# CAN.net
KiCad netlist of a schematic drawn in Altium Designer
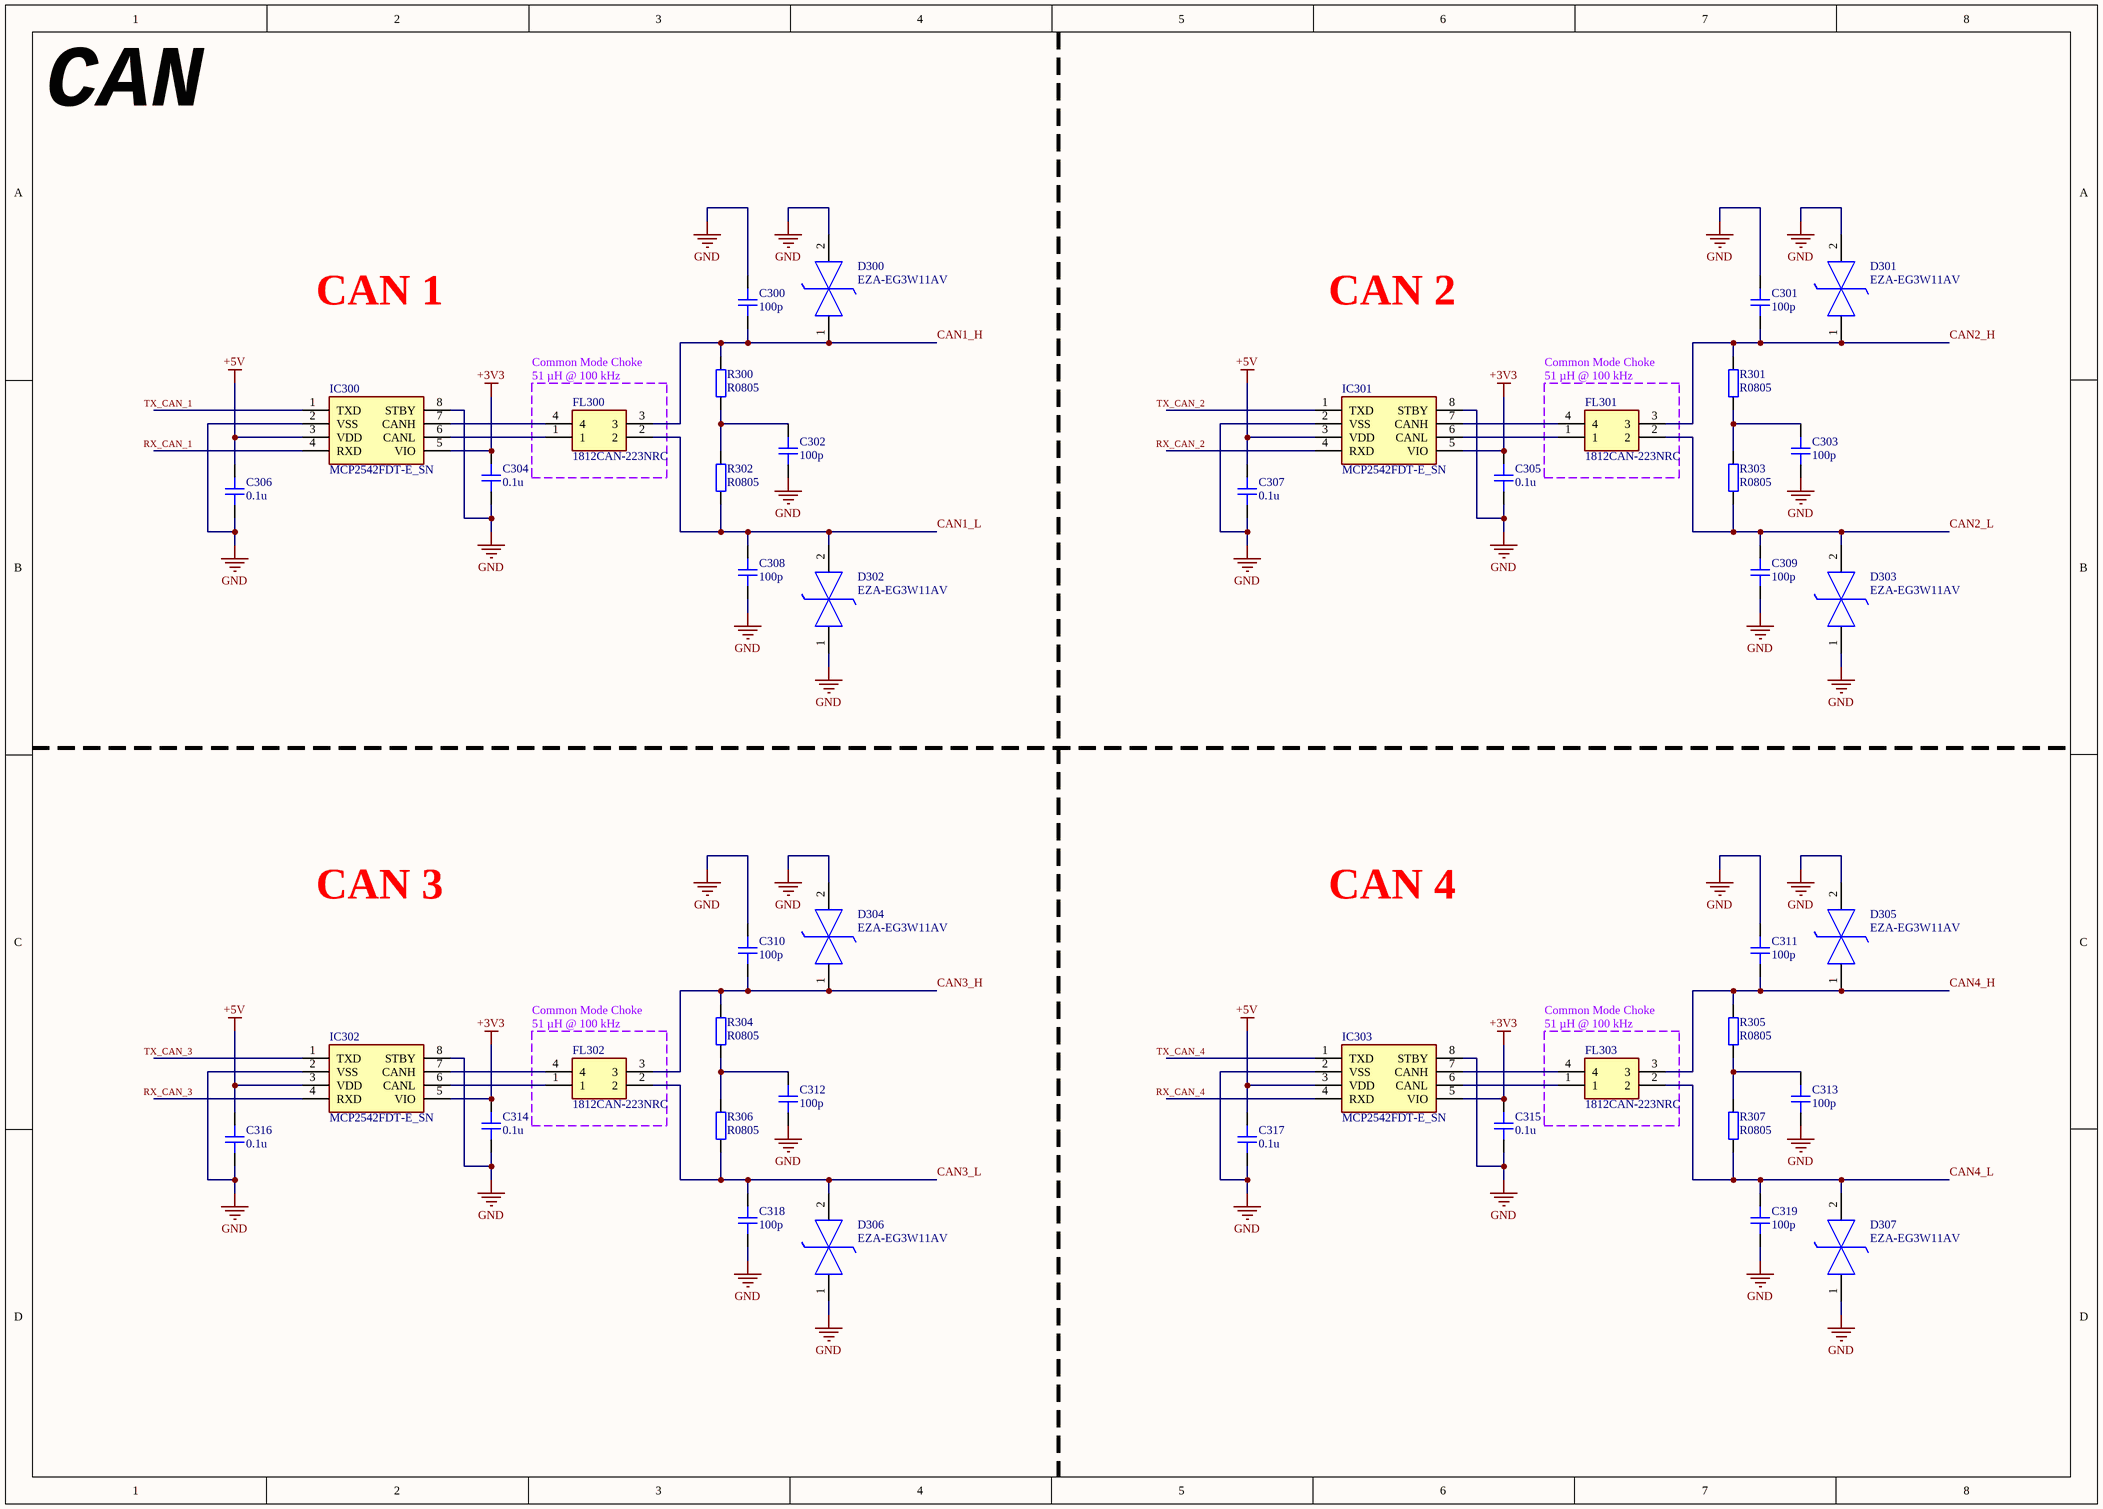
[diagram p0: CAN.SchDoc]

(export (version "E")
  (design (tool "Eeschema 10.0.6"))
  (components
    (comp (ref "C300")
      (value "100p")
      (footprint "CAP_0805")
      (description "Capacitor SMD 0805 10V")
      (libsource (lib "Schematic-Lib-PhilsLab") (part "CAP_0805_10V"))
    )
    (comp (ref "C301")
      (value "100p")
      (footprint "CAP_0805")
      (description "Capacitor SMD 0805 10V")
      (libsource (lib "Schematic-Lib-PhilsLab") (part "CAP_0805_10V"))
    )
    (comp (ref "C302")
      (value "100p")
      (footprint "CAP_0805")
      (description "Capacitor SMD 0805 10V")
      (libsource (lib "Schematic-Lib-PhilsLab") (part "CAP_0805_10V"))
    )
    (comp (ref "C303")
      (value "100p")
      (footprint "CAP_0805")
      (description "Capacitor SMD 0805 10V")
      (libsource (lib "Schematic-Lib-PhilsLab") (part "CAP_0805_10V"))
    )
    (comp (ref "C304")
      (value "0.1u")
      (footprint "CAP_0805")
      (description "Capacitor SMD 0805 10V")
      (libsource (lib "Schematic-Lib-PhilsLab") (part "CAP_0805_10V"))
    )
    (comp (ref "C305")
      (value "0.1u")
      (footprint "CAP_0805")
      (description "Capacitor SMD 0805 10V")
      (libsource (lib "Schematic-Lib-PhilsLab") (part "CAP_0805_10V"))
    )
    (comp (ref "C306")
      (value "0.1u")
      (footprint "CAP_0805")
      (description "Capacitor SMD 0805 10V")
      (libsource (lib "Schematic-Lib-PhilsLab") (part "CAP_0805_10V"))
    )
    (comp (ref "C307")
      (value "0.1u")
      (footprint "CAP_0805")
      (description "Capacitor SMD 0805 10V")
      (libsource (lib "Schematic-Lib-PhilsLab") (part "CAP_0805_10V"))
    )
    (comp (ref "C308")
      (value "100p")
      (footprint "CAP_0805")
      (description "Capacitor SMD 0805 10V")
      (libsource (lib "Schematic-Lib-PhilsLab") (part "CAP_0805_10V"))
    )
    (comp (ref "C309")
      (value "100p")
      (footprint "CAP_0805")
      (description "Capacitor SMD 0805 10V")
      (libsource (lib "Schematic-Lib-PhilsLab") (part "CAP_0805_10V"))
    )
    (comp (ref "C310")
      (value "100p")
      (footprint "CAP_0805")
      (description "Capacitor SMD 0805 10V")
      (libsource (lib "Schematic-Lib-PhilsLab") (part "CAP_0805_10V"))
    )
    (comp (ref "C311")
      (value "100p")
      (footprint "CAP_0805")
      (description "Capacitor SMD 0805 10V")
      (libsource (lib "Schematic-Lib-PhilsLab") (part "CAP_0805_10V"))
    )
    (comp (ref "C312")
      (value "100p")
      (footprint "CAP_0805")
      (description "Capacitor SMD 0805 10V")
      (libsource (lib "Schematic-Lib-PhilsLab") (part "CAP_0805_10V"))
    )
    (comp (ref "C313")
      (value "100p")
      (footprint "CAP_0805")
      (description "Capacitor SMD 0805 10V")
      (libsource (lib "Schematic-Lib-PhilsLab") (part "CAP_0805_10V"))
    )
    (comp (ref "C314")
      (value "0.1u")
      (footprint "CAP_0805")
      (description "Capacitor SMD 0805 10V")
      (libsource (lib "Schematic-Lib-PhilsLab") (part "CAP_0805_10V"))
    )
    (comp (ref "C315")
      (value "0.1u")
      (footprint "CAP_0805")
      (description "Capacitor SMD 0805 10V")
      (libsource (lib "Schematic-Lib-PhilsLab") (part "CAP_0805_10V"))
    )
    (comp (ref "C316")
      (value "0.1u")
      (footprint "CAP_0805")
      (description "Capacitor SMD 0805 10V")
      (libsource (lib "Schematic-Lib-PhilsLab") (part "CAP_0805_10V"))
    )
    (comp (ref "C317")
      (value "0.1u")
      (footprint "CAP_0805")
      (description "Capacitor SMD 0805 10V")
      (libsource (lib "Schematic-Lib-PhilsLab") (part "CAP_0805_10V"))
    )
    (comp (ref "C318")
      (value "100p")
      (footprint "CAP_0805")
      (description "Capacitor SMD 0805 10V")
      (libsource (lib "Schematic-Lib-PhilsLab") (part "CAP_0805_10V"))
    )
    (comp (ref "C319")
      (value "100p")
      (footprint "CAP_0805")
      (description "Capacitor SMD 0805 10V")
      (libsource (lib "Schematic-Lib-PhilsLab") (part "CAP_0805_10V"))
    )
    (comp (ref "D300")
      (value "EZA-EG3W11AV")
      (footprint "EZAEG3W11AV")
      (description "Diode ESD (Bi-directional)")
      (fields (field (name "MOUSER PART NUMBER") "667-EZA-EG3W11AV"))
      (libsource (lib "Pedro_Integrated_Library") (part "EZA-EG3W11AV"))
    )
    (comp (ref "D301")
      (value "EZA-EG3W11AV")
      (footprint "EZAEG3W11AV")
      (description "Diode ESD (Bi-directional)")
      (fields (field (name "MOUSER PART NUMBER") "667-EZA-EG3W11AV"))
      (libsource (lib "Pedro_Integrated_Library") (part "EZA-EG3W11AV"))
    )
    (comp (ref "D302")
      (value "EZA-EG3W11AV")
      (footprint "EZAEG3W11AV")
      (description "Diode ESD (Bi-directional)")
      (fields (field (name "MOUSER PART NUMBER") "667-EZA-EG3W11AV"))
      (libsource (lib "Pedro_Integrated_Library") (part "EZA-EG3W11AV"))
    )
    (comp (ref "D303")
      (value "EZA-EG3W11AV")
      (footprint "EZAEG3W11AV")
      (description "Diode ESD (Bi-directional)")
      (fields (field (name "MOUSER PART NUMBER") "667-EZA-EG3W11AV"))
      (libsource (lib "Pedro_Integrated_Library") (part "EZA-EG3W11AV"))
    )
    (comp (ref "D304")
      (value "EZA-EG3W11AV")
      (footprint "EZAEG3W11AV")
      (description "Diode ESD (Bi-directional)")
      (fields (field (name "MOUSER PART NUMBER") "667-EZA-EG3W11AV"))
      (libsource (lib "Pedro_Integrated_Library") (part "EZA-EG3W11AV"))
    )
    (comp (ref "D305")
      (value "EZA-EG3W11AV")
      (footprint "EZAEG3W11AV")
      (description "Diode ESD (Bi-directional)")
      (fields (field (name "MOUSER PART NUMBER") "667-EZA-EG3W11AV"))
      (libsource (lib "Pedro_Integrated_Library") (part "EZA-EG3W11AV"))
    )
    (comp (ref "D306")
      (value "EZA-EG3W11AV")
      (footprint "EZAEG3W11AV")
      (description "Diode ESD (Bi-directional)")
      (fields (field (name "MOUSER PART NUMBER") "667-EZA-EG3W11AV"))
      (libsource (lib "Pedro_Integrated_Library") (part "EZA-EG3W11AV"))
    )
    (comp (ref "D307")
      (value "EZA-EG3W11AV")
      (footprint "EZAEG3W11AV")
      (description "Diode ESD (Bi-directional)")
      (fields (field (name "MOUSER PART NUMBER") "667-EZA-EG3W11AV"))
      (libsource (lib "Pedro_Integrated_Library") (part "EZA-EG3W11AV"))
    )
    (comp (ref "FL300")
      (value "1812CAN-223NRC")
      (footprint "1812CAN223NRC")
      (description "Filter")
      (fields (field (name "MOUSER PART NUMBER") "994-1812CAN-223NRC"))
      (libsource (lib "Pedro_Integrated_Library") (part "1812CAN-223NRC"))
    )
    (comp (ref "FL301")
      (value "1812CAN-223NRC")
      (footprint "1812CAN223NRC")
      (description "Filter")
      (fields (field (name "MOUSER PART NUMBER") "994-1812CAN-223NRC"))
      (libsource (lib "Pedro_Integrated_Library") (part "1812CAN-223NRC"))
    )
    (comp (ref "FL302")
      (value "1812CAN-223NRC")
      (footprint "1812CAN223NRC")
      (description "Filter")
      (fields (field (name "MOUSER PART NUMBER") "994-1812CAN-223NRC"))
      (libsource (lib "Pedro_Integrated_Library") (part "1812CAN-223NRC"))
    )
    (comp (ref "FL303")
      (value "1812CAN-223NRC")
      (footprint "1812CAN223NRC")
      (description "Filter")
      (fields (field (name "MOUSER PART NUMBER") "994-1812CAN-223NRC"))
      (libsource (lib "Pedro_Integrated_Library") (part "1812CAN-223NRC"))
    )
    (comp (ref "IC300")
      (value "MCP2542FDT-E_SN")
      (footprint "SOIC127P600X175-8N")
      (description "Integrated Circuit")
      (fields
        (field (name "MANUFACTURER_PART_NUMBER") "MCP2542FDT-E/SN")
        (field (name "MOUSER PART NUMBER") "579-MCP2542FDT-E/SN")
      )
      (libsource (lib "*") (part "MCP2542FDT-E_SN"))
    )
    (comp (ref "IC301")
      (value "MCP2542FDT-E_SN")
      (footprint "SOIC127P600X175-8N")
      (description "Integrated Circuit")
      (fields
        (field (name "MANUFACTURER_PART_NUMBER") "MCP2542FDT-E/SN")
        (field (name "MOUSER PART NUMBER") "579-MCP2542FDT-E/SN")
      )
      (libsource (lib "*") (part "MCP2542FDT-E_SN"))
    )
    (comp (ref "IC302")
      (value "MCP2542FDT-E_SN")
      (footprint "SOIC127P600X175-8N")
      (description "Integrated Circuit")
      (fields
        (field (name "MANUFACTURER_PART_NUMBER") "MCP2542FDT-E/SN")
        (field (name "MOUSER PART NUMBER") "579-MCP2542FDT-E/SN")
      )
      (libsource (lib "*") (part "MCP2542FDT-E_SN"))
    )
    (comp (ref "IC303")
      (value "MCP2542FDT-E_SN")
      (footprint "SOIC127P600X175-8N")
      (description "Integrated Circuit")
      (fields
        (field (name "MANUFACTURER_PART_NUMBER") "MCP2542FDT-E/SN")
        (field (name "MOUSER PART NUMBER") "579-MCP2542FDT-E/SN")
      )
      (libsource (lib "*") (part "MCP2542FDT-E_SN"))
    )
    (comp (ref "R300")
      (value "R0805")
      (footprint "RES_0805")
      (description "Resistor SMD 0805")
      (libsource (lib "Schematic-Lib-PhilsLab") (part "RES_0805"))
    )
    (comp (ref "R301")
      (value "R0805")
      (footprint "RES_0805")
      (description "Resistor SMD 0805")
      (libsource (lib "Schematic-Lib-PhilsLab") (part "RES_0805"))
    )
    (comp (ref "R302")
      (value "R0805")
      (footprint "RES_0805")
      (description "Resistor SMD 0805")
      (libsource (lib "Schematic-Lib-PhilsLab") (part "RES_0805"))
    )
    (comp (ref "R303")
      (value "R0805")
      (footprint "RES_0805")
      (description "Resistor SMD 0805")
      (libsource (lib "Schematic-Lib-PhilsLab") (part "RES_0805"))
    )
    (comp (ref "R304")
      (value "R0805")
      (footprint "RES_0805")
      (description "Resistor SMD 0805")
      (libsource (lib "Schematic-Lib-PhilsLab") (part "RES_0805"))
    )
    (comp (ref "R305")
      (value "R0805")
      (footprint "RES_0805")
      (description "Resistor SMD 0805")
      (libsource (lib "Schematic-Lib-PhilsLab") (part "RES_0805"))
    )
    (comp (ref "R306")
      (value "R0805")
      (footprint "RES_0805")
      (description "Resistor SMD 0805")
      (libsource (lib "Schematic-Lib-PhilsLab") (part "RES_0805"))
    )
    (comp (ref "R307")
      (value "R0805")
      (footprint "RES_0805")
      (description "Resistor SMD 0805")
      (libsource (lib "Schematic-Lib-PhilsLab") (part "RES_0805"))
    )
  )
  (nets
    (net (code "1") (name "+3V3") (class "Default")
      (node (ref "C304") (pin "2") (pinfunction "2_2") (pintype "passive"))
      (node (ref "C305") (pin "2") (pinfunction "2_2") (pintype "passive"))
      (node (ref "C314") (pin "2") (pinfunction "2_2") (pintype "passive"))
      (node (ref "C315") (pin "2") (pinfunction "2_2") (pintype "passive"))
      (node (ref "IC300") (pin "5") (pinfunction "VIO_5") (pintype "passive"))
      (node (ref "IC301") (pin "5") (pinfunction "VIO_5") (pintype "passive"))
      (node (ref "IC302") (pin "5") (pinfunction "VIO_5") (pintype "passive"))
      (node (ref "IC303") (pin "5") (pinfunction "VIO_5") (pintype "passive"))
    )
    (net (code "2") (name "+5V") (class "Default")
      (node (ref "C306") (pin "2") (pinfunction "2_2") (pintype "passive"))
      (node (ref "C307") (pin "2") (pinfunction "2_2") (pintype "passive"))
      (node (ref "C316") (pin "2") (pinfunction "2_2") (pintype "passive"))
      (node (ref "C317") (pin "2") (pinfunction "2_2") (pintype "passive"))
      (node (ref "IC300") (pin "3") (pinfunction "VDD_3") (pintype "passive"))
      (node (ref "IC301") (pin "3") (pinfunction "VDD_3") (pintype "passive"))
      (node (ref "IC302") (pin "3") (pinfunction "VDD_3") (pintype "passive"))
      (node (ref "IC303") (pin "3") (pinfunction "VDD_3") (pintype "passive"))
    )
    (net (code "3") (name "/CAN1_H") (class "Default")
      (node (ref "C300") (pin "2") (pinfunction "2_2") (pintype "passive"))
      (node (ref "D300") (pin "1") (pinfunction "K1_1") (pintype "passive"))
      (node (ref "FL300") (pin "3") (pinfunction "3_3") (pintype "passive"))
      (node (ref "R300") (pin "2") (pinfunction "2_2") (pintype "passive"))
    )
    (net (code "4") (name "/CAN1_L") (class "Default")
      (node (ref "C308") (pin "1") (pinfunction "1_1") (pintype "passive"))
      (node (ref "D302") (pin "2") (pinfunction "K2_2") (pintype "passive"))
      (node (ref "FL300") (pin "2") (pinfunction "2_2") (pintype "passive"))
      (node (ref "R302") (pin "1") (pinfunction "1_1") (pintype "passive"))
    )
    (net (code "5") (name "/CAN2_H") (class "Default")
      (node (ref "C301") (pin "2") (pinfunction "2_2") (pintype "passive"))
      (node (ref "D301") (pin "1") (pinfunction "K1_1") (pintype "passive"))
      (node (ref "FL301") (pin "3") (pinfunction "3_3") (pintype "passive"))
      (node (ref "R301") (pin "2") (pinfunction "2_2") (pintype "passive"))
    )
    (net (code "6") (name "/CAN2_L") (class "Default")
      (node (ref "C309") (pin "1") (pinfunction "1_1") (pintype "passive"))
      (node (ref "D303") (pin "2") (pinfunction "K2_2") (pintype "passive"))
      (node (ref "FL301") (pin "2") (pinfunction "2_2") (pintype "passive"))
      (node (ref "R303") (pin "1") (pinfunction "1_1") (pintype "passive"))
    )
    (net (code "7") (name "/CAN3_H") (class "Default")
      (node (ref "C310") (pin "2") (pinfunction "2_2") (pintype "passive"))
      (node (ref "D304") (pin "1") (pinfunction "K1_1") (pintype "passive"))
      (node (ref "FL302") (pin "3") (pinfunction "3_3") (pintype "passive"))
      (node (ref "R304") (pin "2") (pinfunction "2_2") (pintype "passive"))
    )
    (net (code "8") (name "/CAN3_L") (class "Default")
      (node (ref "C318") (pin "1") (pinfunction "1_1") (pintype "passive"))
      (node (ref "D306") (pin "2") (pinfunction "K2_2") (pintype "passive"))
      (node (ref "FL302") (pin "2") (pinfunction "2_2") (pintype "passive"))
      (node (ref "R306") (pin "1") (pinfunction "1_1") (pintype "passive"))
    )
    (net (code "9") (name "/CAN4_H") (class "Default")
      (node (ref "C311") (pin "2") (pinfunction "2_2") (pintype "passive"))
      (node (ref "D305") (pin "1") (pinfunction "K1_1") (pintype "passive"))
      (node (ref "FL303") (pin "3") (pinfunction "3_3") (pintype "passive"))
      (node (ref "R305") (pin "2") (pinfunction "2_2") (pintype "passive"))
    )
    (net (code "10") (name "/CAN4_L") (class "Default")
      (node (ref "C319") (pin "1") (pinfunction "1_1") (pintype "passive"))
      (node (ref "D307") (pin "2") (pinfunction "K2_2") (pintype "passive"))
      (node (ref "FL303") (pin "2") (pinfunction "2_2") (pintype "passive"))
      (node (ref "R307") (pin "1") (pinfunction "1_1") (pintype "passive"))
    )
    (net (code "11") (name "/RX_CAN_1") (class "Default")
      (node (ref "IC300") (pin "4") (pinfunction "RXD_4") (pintype "passive"))
    )
    (net (code "12") (name "/RX_CAN_2") (class "Default")
      (node (ref "IC301") (pin "4") (pinfunction "RXD_4") (pintype "passive"))
    )
    (net (code "13") (name "/RX_CAN_3") (class "Default")
      (node (ref "IC302") (pin "4") (pinfunction "RXD_4") (pintype "passive"))
    )
    (net (code "14") (name "/RX_CAN_4") (class "Default")
      (node (ref "IC303") (pin "4") (pinfunction "RXD_4") (pintype "passive"))
    )
    (net (code "15") (name "/TX_CAN_1") (class "Default")
      (node (ref "IC300") (pin "1") (pinfunction "TXD_1") (pintype "passive"))
    )
    (net (code "16") (name "/TX_CAN_2") (class "Default")
      (node (ref "IC301") (pin "1") (pinfunction "TXD_1") (pintype "passive"))
    )
    (net (code "17") (name "/TX_CAN_3") (class "Default")
      (node (ref "IC302") (pin "1") (pinfunction "TXD_1") (pintype "passive"))
    )
    (net (code "18") (name "/TX_CAN_4") (class "Default")
      (node (ref "IC303") (pin "1") (pinfunction "TXD_1") (pintype "passive"))
    )
    (net (code "19") (name "GND") (class "Default")
      (node (ref "C300") (pin "1") (pinfunction "1_1") (pintype "passive"))
      (node (ref "C301") (pin "1") (pinfunction "1_1") (pintype "passive"))
      (node (ref "C302") (pin "2") (pinfunction "2_2") (pintype "passive"))
      (node (ref "C303") (pin "2") (pinfunction "2_2") (pintype "passive"))
      (node (ref "C304") (pin "1") (pinfunction "1_1") (pintype "passive"))
      (node (ref "C305") (pin "1") (pinfunction "1_1") (pintype "passive"))
      (node (ref "C306") (pin "1") (pinfunction "1_1") (pintype "passive"))
      (node (ref "C307") (pin "1") (pinfunction "1_1") (pintype "passive"))
      (node (ref "C308") (pin "2") (pinfunction "2_2") (pintype "passive"))
      (node (ref "C309") (pin "2") (pinfunction "2_2") (pintype "passive"))
      (node (ref "C310") (pin "1") (pinfunction "1_1") (pintype "passive"))
      (node (ref "C311") (pin "1") (pinfunction "1_1") (pintype "passive"))
      (node (ref "C312") (pin "2") (pinfunction "2_2") (pintype "passive"))
      (node (ref "C313") (pin "2") (pinfunction "2_2") (pintype "passive"))
      (node (ref "C314") (pin "1") (pinfunction "1_1") (pintype "passive"))
      (node (ref "C315") (pin "1") (pinfunction "1_1") (pintype "passive"))
      (node (ref "C316") (pin "1") (pinfunction "1_1") (pintype "passive"))
      (node (ref "C317") (pin "1") (pinfunction "1_1") (pintype "passive"))
      (node (ref "C318") (pin "2") (pinfunction "2_2") (pintype "passive"))
      (node (ref "C319") (pin "2") (pinfunction "2_2") (pintype "passive"))
      (node (ref "D300") (pin "2") (pinfunction "K2_2") (pintype "passive"))
      (node (ref "D301") (pin "2") (pinfunction "K2_2") (pintype "passive"))
      (node (ref "D302") (pin "1") (pinfunction "K1_1") (pintype "passive"))
      (node (ref "D303") (pin "1") (pinfunction "K1_1") (pintype "passive"))
      (node (ref "D304") (pin "2") (pinfunction "K2_2") (pintype "passive"))
      (node (ref "D305") (pin "2") (pinfunction "K2_2") (pintype "passive"))
      (node (ref "D306") (pin "1") (pinfunction "K1_1") (pintype "passive"))
      (node (ref "D307") (pin "1") (pinfunction "K1_1") (pintype "passive"))
      (node (ref "IC300") (pin "2") (pinfunction "VSS_2") (pintype "passive"))
      (node (ref "IC300") (pin "8") (pinfunction "STBY_8") (pintype "passive"))
      (node (ref "IC301") (pin "2") (pinfunction "VSS_2") (pintype "passive"))
      (node (ref "IC301") (pin "8") (pinfunction "STBY_8") (pintype "passive"))
      (node (ref "IC302") (pin "2") (pinfunction "VSS_2") (pintype "passive"))
      (node (ref "IC302") (pin "8") (pinfunction "STBY_8") (pintype "passive"))
      (node (ref "IC303") (pin "2") (pinfunction "VSS_2") (pintype "passive"))
      (node (ref "IC303") (pin "8") (pinfunction "STBY_8") (pintype "passive"))
    )
    (net (code "20") (name "Net-(C302-Pad1)") (class "Default")
      (node (ref "C302") (pin "1") (pinfunction "1_1") (pintype "passive"))
      (node (ref "R300") (pin "1") (pinfunction "1_1") (pintype "passive"))
      (node (ref "R302") (pin "2") (pinfunction "2_2") (pintype "passive"))
    )
    (net (code "21") (name "Net-(C303-Pad1)") (class "Default")
      (node (ref "C303") (pin "1") (pinfunction "1_1") (pintype "passive"))
      (node (ref "R301") (pin "1") (pinfunction "1_1") (pintype "passive"))
      (node (ref "R303") (pin "2") (pinfunction "2_2") (pintype "passive"))
    )
    (net (code "22") (name "Net-(C312-Pad1)") (class "Default")
      (node (ref "C312") (pin "1") (pinfunction "1_1") (pintype "passive"))
      (node (ref "R304") (pin "1") (pinfunction "1_1") (pintype "passive"))
      (node (ref "R306") (pin "2") (pinfunction "2_2") (pintype "passive"))
    )
    (net (code "23") (name "Net-(C313-Pad1)") (class "Default")
      (node (ref "C313") (pin "1") (pinfunction "1_1") (pintype "passive"))
      (node (ref "R305") (pin "1") (pinfunction "1_1") (pintype "passive"))
      (node (ref "R307") (pin "2") (pinfunction "2_2") (pintype "passive"))
    )
    (net (code "24") (name "Net-(IC300-CANH)") (class "Default")
      (node (ref "FL300") (pin "4") (pinfunction "4_4") (pintype "passive"))
      (node (ref "IC300") (pin "7") (pinfunction "CANH_7") (pintype "passive"))
    )
    (net (code "25") (name "Net-(IC300-CANL)") (class "Default")
      (node (ref "FL300") (pin "1") (pinfunction "1_1") (pintype "passive"))
      (node (ref "IC300") (pin "6") (pinfunction "CANL_6") (pintype "passive"))
    )
    (net (code "26") (name "Net-(IC301-CANH)") (class "Default")
      (node (ref "FL301") (pin "4") (pinfunction "4_4") (pintype "passive"))
      (node (ref "IC301") (pin "7") (pinfunction "CANH_7") (pintype "passive"))
    )
    (net (code "27") (name "Net-(IC301-CANL)") (class "Default")
      (node (ref "FL301") (pin "1") (pinfunction "1_1") (pintype "passive"))
      (node (ref "IC301") (pin "6") (pinfunction "CANL_6") (pintype "passive"))
    )
    (net (code "28") (name "Net-(IC302-CANH)") (class "Default")
      (node (ref "FL302") (pin "4") (pinfunction "4_4") (pintype "passive"))
      (node (ref "IC302") (pin "7") (pinfunction "CANH_7") (pintype "passive"))
    )
    (net (code "29") (name "Net-(IC302-CANL)") (class "Default")
      (node (ref "FL302") (pin "1") (pinfunction "1_1") (pintype "passive"))
      (node (ref "IC302") (pin "6") (pinfunction "CANL_6") (pintype "passive"))
    )
    (net (code "30") (name "Net-(IC303-CANH)") (class "Default")
      (node (ref "FL303") (pin "4") (pinfunction "4_4") (pintype "passive"))
      (node (ref "IC303") (pin "7") (pinfunction "CANH_7") (pintype "passive"))
    )
    (net (code "31") (name "Net-(IC303-CANL)") (class "Default")
      (node (ref "FL303") (pin "1") (pinfunction "1_1") (pintype "passive"))
      (node (ref "IC303") (pin "6") (pinfunction "CANL_6") (pintype "passive"))
    )
  )
)
